# SCH_PCB-Business-Card_2025-08-18.net
KiCad netlist of a schematic drawn in EasyEDA
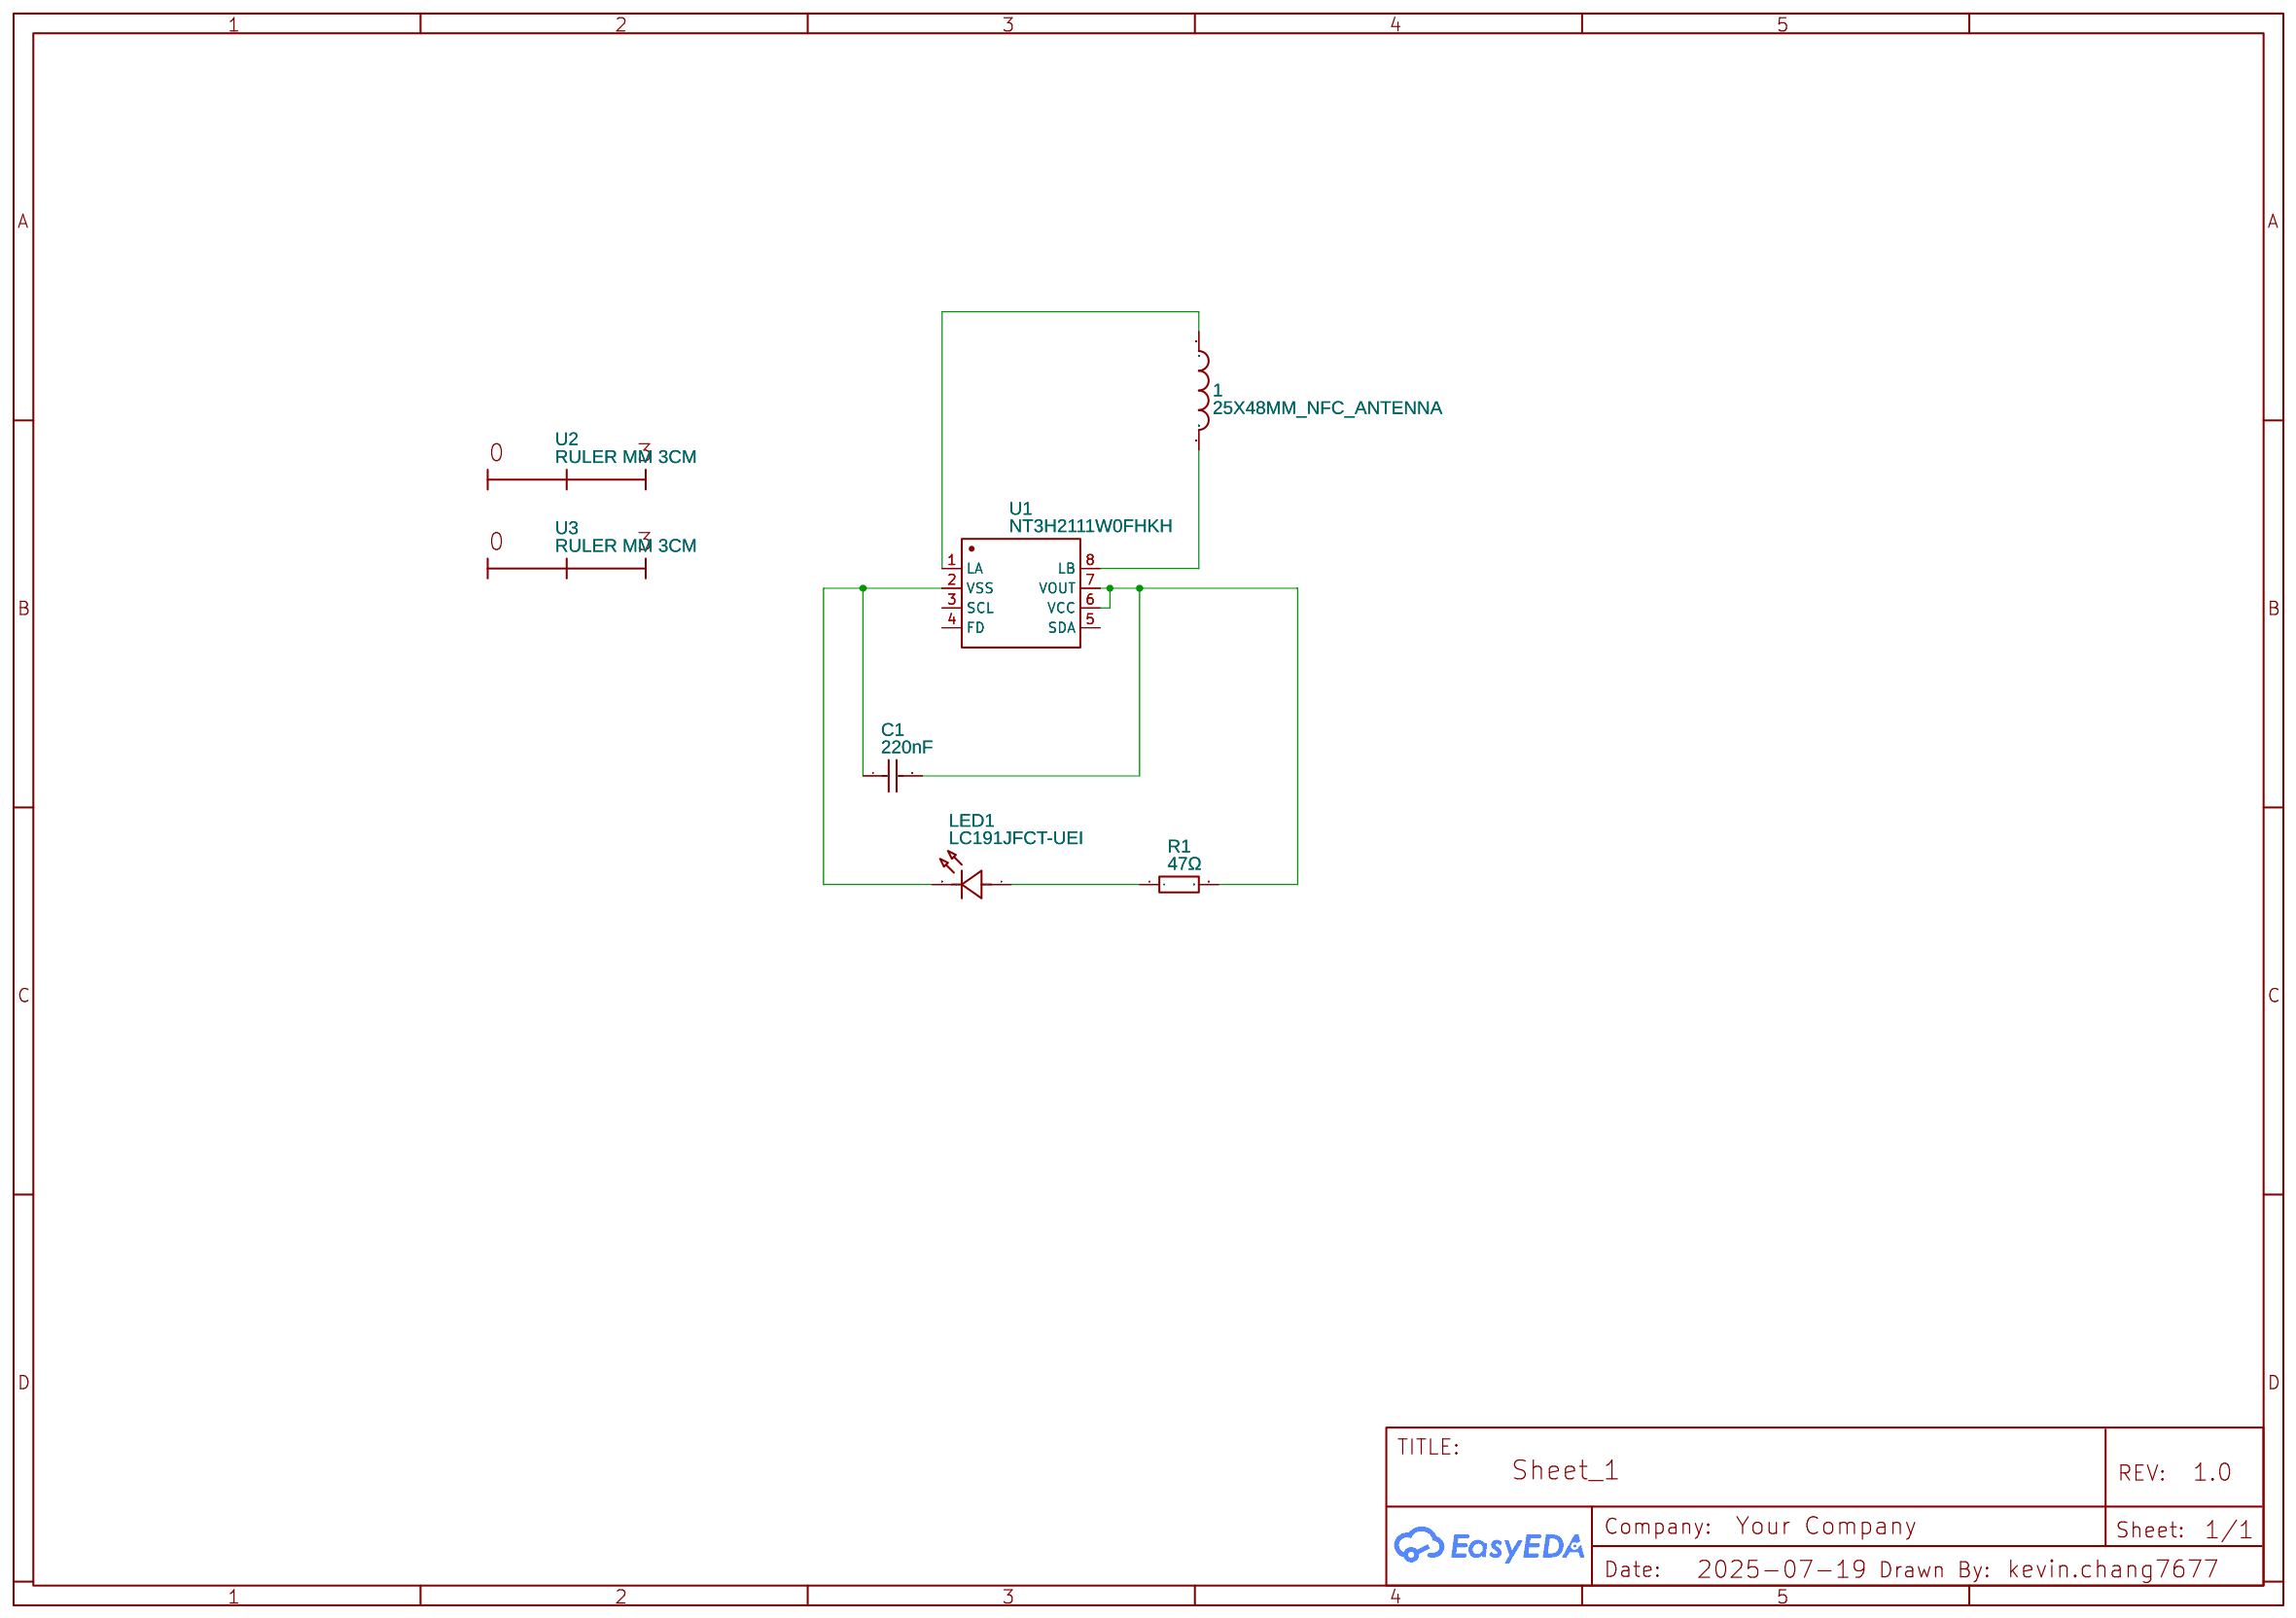
[diagram p0: schematic sheet]

(export (version "E")
  (design (tool "Eeschema 10.0.6"))
  (components
    (comp (ref "1") (value "25X48MM_NFC_ANTENNA") (libsource (lib "") (part "25X48MM_NFC_ANTENNA")))
    (comp (ref "C1")
      (value "220nF")
      (fields
        (field (name "Manufacturer Part") "CL10B224KA8NNNC")
        (field (name "Manufacturer") "SAMSUNG(三星)")
      )
      (libsource (lib "") (part "CL10B224KA8NNNC"))
    )
    (comp (ref "LED1")
      (value "LC191JFCT-UEI")
      (fields (field (name "Manufacturer") "PARALIGHT(光鼎)"))
      (libsource (lib "") (part "LC191JFCT-UEI"))
    )
    (comp (ref "R1")
      (value "47Ω")
      (fields
        (field (name "Manufacturer Part") "0603WAF470JT5E")
        (field (name "Manufacturer") "UNI-ROYAL(厚声)")
      )
      (libsource (lib "") (part "0603WAF470JT5E"))
    )
    (comp (ref "U1")
      (value "NT3H2111W0FHKH")
      (fields (field (name "Manufacturer") "NXP(恩智浦)"))
      (libsource (lib "") (part "NT3H2111W0FHKH"))
    )
    (comp (ref "U2") (value "RULER MM 3CM") (libsource (lib "") (part "RULER MM 3CM")))
    (comp (ref "U3") (value "RULER MM 3CM") (libsource (lib "") (part "RULER MM 3CM")))
  )
  (nets
    (net (code "1") (name "Net-(LED1-A)") (class "Default")
      (node (ref "LED1") (pin "1") (pinfunction "A_1") (pintype "unspecified"))
      (node (ref "R1") (pin "1") (pinfunction "1_1") (pintype "input"))
    )
    (net (code "2") (name "Net-(LED1-K)") (class "Default")
      (node (ref "C1") (pin "1") (pinfunction "1_1") (pintype "input"))
      (node (ref "LED1") (pin "2") (pinfunction "K_2") (pintype "unspecified"))
      (node (ref "U1") (pin "2") (pinfunction "VSS_2") (pintype "unspecified"))
    )
    (net (code "3") (name "Net-(U1-LA)") (class "Default")
      (node (ref "1") (pin "P$1") (pinfunction "P$1_P$1") (pintype "bidirectional"))
      (node (ref "U1") (pin "1") (pinfunction "LA_1") (pintype "unspecified"))
    )
    (net (code "4") (name "Net-(U1-LB)") (class "Default")
      (node (ref "1") (pin "P$2") (pinfunction "P$2_P$2") (pintype "bidirectional"))
      (node (ref "U1") (pin "8") (pinfunction "LB_8") (pintype "unspecified"))
    )
    (net (code "5") (name "Net-(U1-VCC)") (class "Default")
      (node (ref "C1") (pin "2") (pinfunction "2_2") (pintype "input"))
      (node (ref "R1") (pin "2") (pinfunction "2_2") (pintype "input"))
      (node (ref "U1") (pin "6") (pinfunction "VCC_6") (pintype "unspecified"))
      (node (ref "U1") (pin "7") (pinfunction "VOUT_7") (pintype "unspecified"))
    )
    (net (code "6") (name "unconnected-(U1-FD-Pad4)") (class "Default")
      (node (ref "U1") (pin "4") (pinfunction "FD_4") (pintype "unspecified"))
    )
    (net (code "7") (name "unconnected-(U1-SCL-Pad3)") (class "Default")
      (node (ref "U1") (pin "3") (pinfunction "SCL_3") (pintype "unspecified"))
    )
    (net (code "8") (name "unconnected-(U1-SDA-Pad5)") (class "Default")
      (node (ref "U1") (pin "5") (pinfunction "SDA_5") (pintype "unspecified"))
    )
  )
)
